# SPI_FRAM_Rev_C.net
KiCad netlist of a schematic drawn in EAGLE
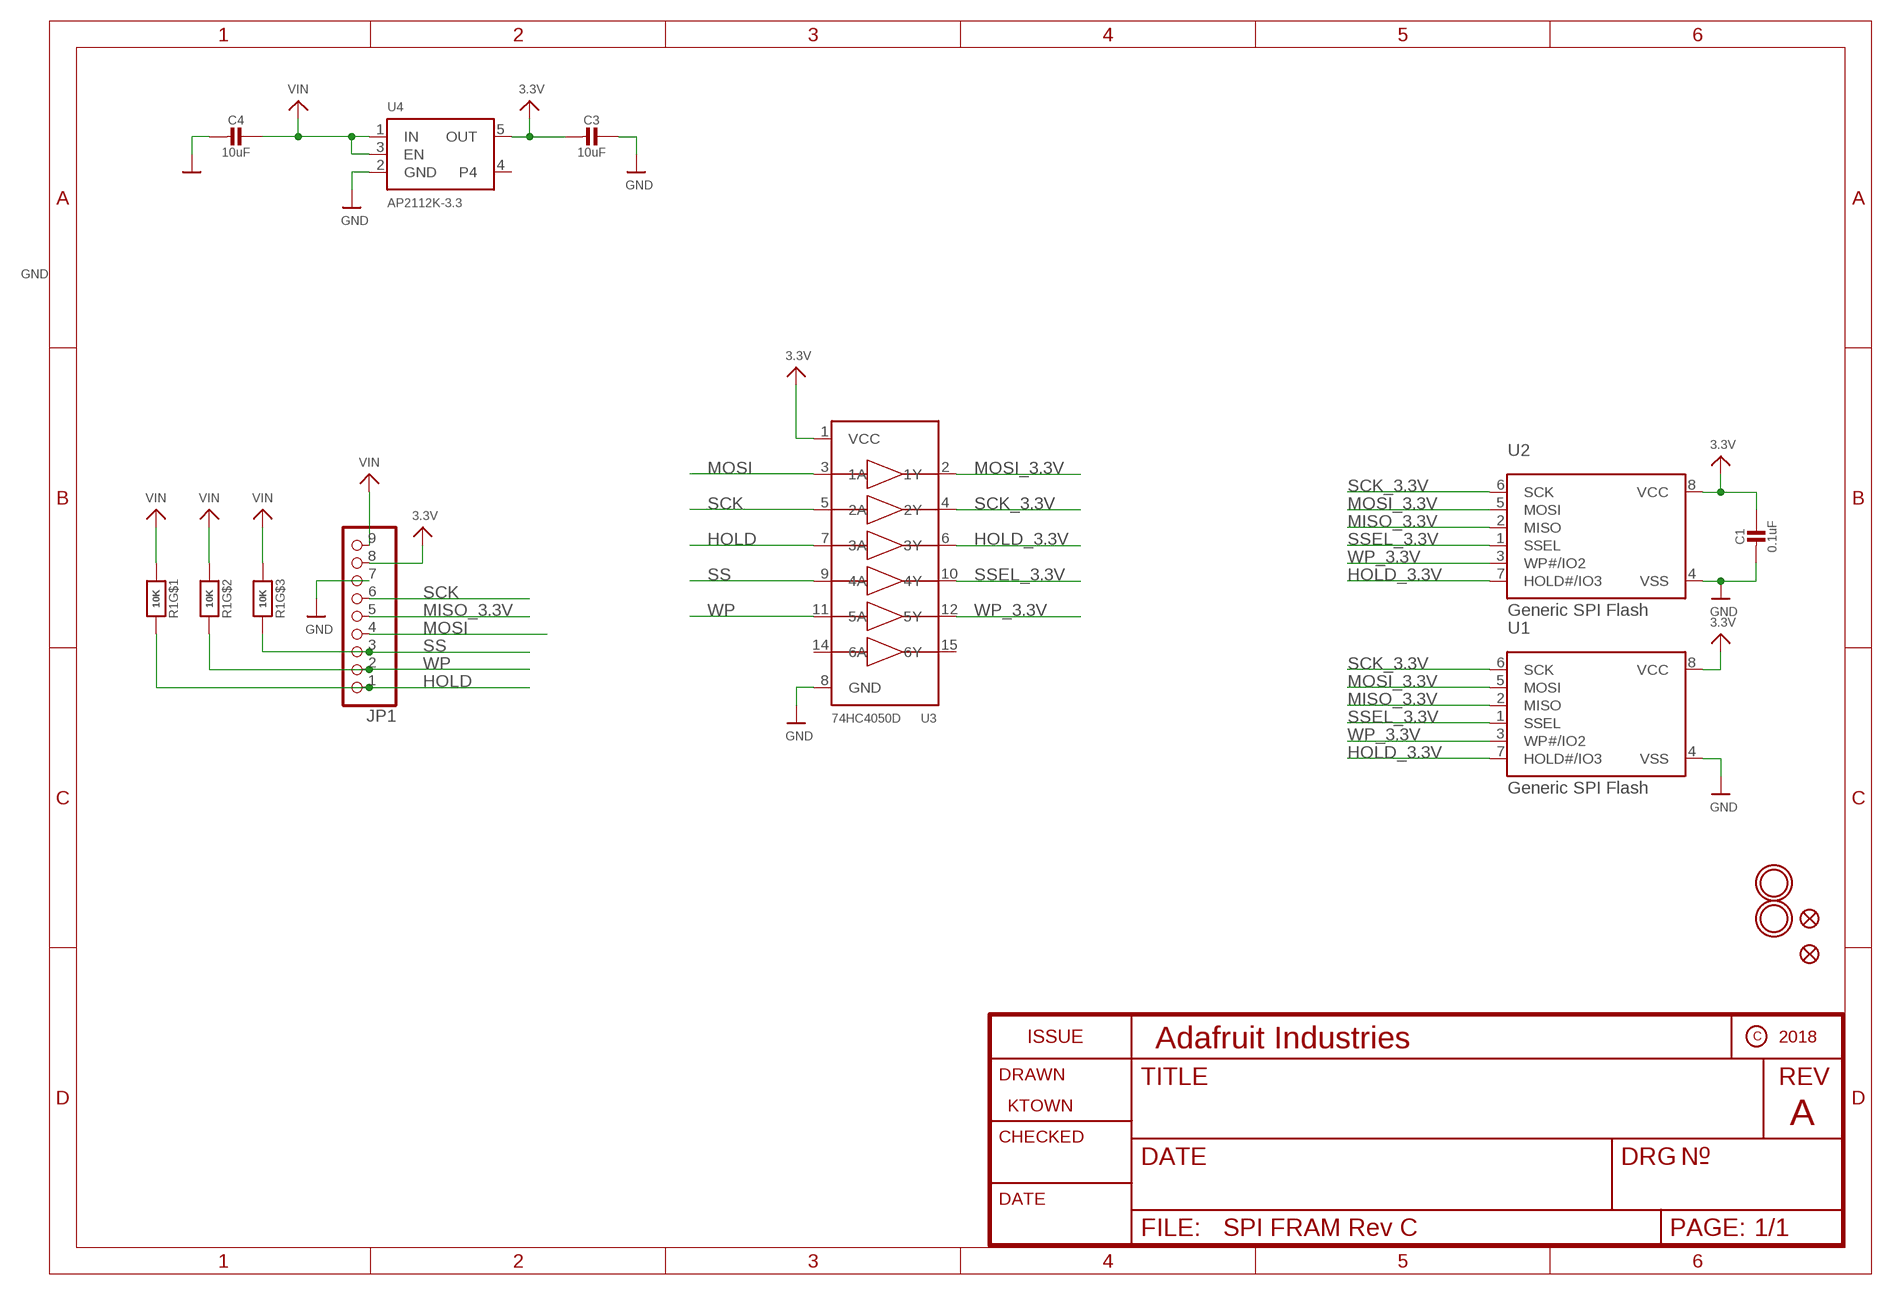
[diagram p0: schematic, sheet 1]

(export (version "E")
  (design (tool "Eeschema 10.0.6"))
  (components
    (comp (ref "C1")
      (value "0.1uF")
      (footprint "eagle-import:0603-NO")
      (libsource (lib "eagle-import") (part "CAP_CERAMIC0603_NO"))
    )
    (comp (ref "C3")
      (value "10uF")
      (footprint "eagle-import:0805-NO")
      (libsource (lib "eagle-import") (part "CAP_CERAMIC0805-NOOUTLINE"))
    )
    (comp (ref "C4")
      (value "10uF")
      (footprint "eagle-import:0805-NO")
      (libsource (lib "eagle-import") (part "CAP_CERAMIC0805-NOOUTLINE"))
    )
    (comp (ref "FID2")
      (value "FIDUCIAL_1MM")
      (footprint "eagle-import:FIDUCIAL_1MM")
      (libsource (lib "eagle-import") (part "FIDUCIAL_1MM"))
    )
    (comp (ref "FID3")
      (value "FIDUCIAL_1MM")
      (footprint "eagle-import:FIDUCIAL_1MM")
      (libsource (lib "eagle-import") (part "FIDUCIAL_1MM"))
    )
    (comp (ref "JP1")
      (value "HEADER-1X970MIL")
      (footprint "eagle-import:1X09_ROUND_70")
      (libsource (lib "eagle-import") (part "HEADER-1X970MIL"))
    )
    (comp (ref "R1")
      (value "10K")
      (footprint "eagle-import:RESPACK_4X0603")
      (libsource (lib "eagle-import") (part "RESISTOR_4PACK"))
    )
    (comp (ref "U$16")
      (value "MOUNTINGHOLE2.5")
      (footprint "eagle-import:MOUNTINGHOLE_2.5_PLATED")
      (libsource (lib "eagle-import") (part "MOUNTINGHOLE2.5"))
    )
    (comp (ref "U$17")
      (value "MOUNTINGHOLE2.5")
      (footprint "eagle-import:MOUNTINGHOLE_2.5_PLATED")
      (libsource (lib "eagle-import") (part "MOUNTINGHOLE2.5"))
    )
    (comp (ref "U1")
      (value "Generic SPI Flash")
      (footprint "eagle-import:SOIC8_208MIL")
      (libsource (lib "eagle-import") (part "SPIFLASH_8PIN208MIL"))
    )
    (comp (ref "U2")
      (value "Generic SPI Flash")
      (footprint "eagle-import:USON8")
      (libsource (lib "eagle-import") (part "SPIFLASH_8PINUX"))
    )
    (comp (ref "U3")
      (value "74HC4050D")
      (footprint "eagle-import:TSSOP16")
      (libsource (lib "eagle-import") (part "74HC4050DTSSOP"))
    )
    (comp (ref "U4")
      (value "AP2112K-3.3")
      (footprint "eagle-import:SOT23-5")
      (libsource (lib "eagle-import") (part "VREG_SOT23-5"))
    )
  )
  (nets
    (net (code "1") (name "/HOLD") (class "Default")
      (node (ref "JP1") (pin "1") (pinfunction "1_1") (pintype "passive"))
      (node (ref "R1") (pin "8") (pinfunction "2_8") (pintype "passive"))
      (node (ref "U3") (pin "7") (pinfunction "3A_7") (pintype "bidirectional"))
    )
    (net (code "2") (name "/HOLD_3.3V") (class "Default")
      (node (ref "U1") (pin "7") (pinfunction "HOLD#/IO3_7") (pintype "bidirectional"))
      (node (ref "U2") (pin "7") (pinfunction "HOLD#/IO3_7") (pintype "bidirectional"))
      (node (ref "U3") (pin "6") (pinfunction "3Y_6") (pintype "bidirectional"))
    )
    (net (code "3") (name "/MISO_3.3V") (class "Default")
      (node (ref "JP1") (pin "5") (pinfunction "5_5") (pintype "passive"))
      (node (ref "U1") (pin "2") (pinfunction "MISO_2") (pintype "bidirectional"))
      (node (ref "U2") (pin "2") (pinfunction "MISO_2") (pintype "bidirectional"))
    )
    (net (code "4") (name "/MOSI") (class "Default")
      (node (ref "JP1") (pin "4") (pinfunction "4_4") (pintype "passive"))
      (node (ref "U3") (pin "3") (pinfunction "1A_3") (pintype "bidirectional"))
    )
    (net (code "5") (name "/MOSI_3.3V") (class "Default")
      (node (ref "U1") (pin "5") (pinfunction "MOSI_5") (pintype "bidirectional"))
      (node (ref "U2") (pin "5") (pinfunction "MOSI_5") (pintype "bidirectional"))
      (node (ref "U3") (pin "2") (pinfunction "1Y_2") (pintype "bidirectional"))
    )
    (net (code "6") (name "/SCK") (class "Default")
      (node (ref "JP1") (pin "6") (pinfunction "6_6") (pintype "passive"))
      (node (ref "U3") (pin "5") (pinfunction "2A_5") (pintype "bidirectional"))
    )
    (net (code "7") (name "/SCK_3.3V") (class "Default")
      (node (ref "U1") (pin "6") (pinfunction "SCK_6") (pintype "bidirectional"))
      (node (ref "U2") (pin "6") (pinfunction "SCK_6") (pintype "bidirectional"))
      (node (ref "U3") (pin "4") (pinfunction "2Y_4") (pintype "bidirectional"))
    )
    (net (code "8") (name "/SS") (class "Default")
      (node (ref "JP1") (pin "3") (pinfunction "3_3") (pintype "passive"))
      (node (ref "R1") (pin "6") (pinfunction "2_6") (pintype "passive"))
      (node (ref "U3") (pin "9") (pinfunction "4A_9") (pintype "bidirectional"))
    )
    (net (code "9") (name "/SSEL_3.3V") (class "Default")
      (node (ref "U1") (pin "1") (pinfunction "SSEL_1") (pintype "bidirectional"))
      (node (ref "U2") (pin "1") (pinfunction "SSEL_1") (pintype "bidirectional"))
      (node (ref "U3") (pin "10") (pinfunction "4Y_10") (pintype "bidirectional"))
    )
    (net (code "10") (name "/WP") (class "Default")
      (node (ref "JP1") (pin "2") (pinfunction "2_2") (pintype "passive"))
      (node (ref "R1") (pin "7") (pinfunction "2_7") (pintype "passive"))
      (node (ref "U3") (pin "11") (pinfunction "5A_11") (pintype "bidirectional"))
    )
    (net (code "11") (name "/WP_3.3V") (class "Default")
      (node (ref "U1") (pin "3") (pinfunction "WP#/IO2_3") (pintype "bidirectional"))
      (node (ref "U2") (pin "3") (pinfunction "WP#/IO2_3") (pintype "bidirectional"))
      (node (ref "U3") (pin "12") (pinfunction "5Y_12") (pintype "bidirectional"))
    )
    (net (code "12") (name "3.3V") (class "Default")
      (node (ref "C1") (pin "1") (pinfunction "1_1") (pintype "passive"))
      (node (ref "C3") (pin "2") (pinfunction "2_2") (pintype "passive"))
      (node (ref "JP1") (pin "8") (pinfunction "8_8") (pintype "passive"))
      (node (ref "U1") (pin "8") (pinfunction "VCC_8") (pintype "bidirectional"))
      (node (ref "U2") (pin "8") (pinfunction "VCC_8") (pintype "bidirectional"))
      (node (ref "U3") (pin "1") (pinfunction "VCC_1") (pintype "bidirectional"))
      (node (ref "U4") (pin "5") (pinfunction "OUT_5") (pintype "power_in"))
    )
    (net (code "13") (name "GND") (class "Default")
      (node (ref "C1") (pin "2") (pinfunction "2_2") (pintype "passive"))
      (node (ref "C3") (pin "1") (pinfunction "1_1") (pintype "passive"))
      (node (ref "C4") (pin "2") (pinfunction "2_2") (pintype "passive"))
      (node (ref "JP1") (pin "7") (pinfunction "7_7") (pintype "passive"))
      (node (ref "U1") (pin "4") (pinfunction "VSS_4") (pintype "bidirectional"))
      (node (ref "U2") (pin "4") (pinfunction "VSS_4") (pintype "bidirectional"))
      (node (ref "U3") (pin "8") (pinfunction "GND_8") (pintype "bidirectional"))
      (node (ref "U4") (pin "2") (pinfunction "GND_2") (pintype "power_in"))
    )
    (net (code "14") (name "VIN") (class "Default")
      (node (ref "C4") (pin "1") (pinfunction "1_1") (pintype "passive"))
      (node (ref "JP1") (pin "9") (pinfunction "9_9") (pintype "passive"))
      (node (ref "R1") (pin "1") (pinfunction "1_1") (pintype "passive"))
      (node (ref "R1") (pin "2") (pinfunction "1_2") (pintype "passive"))
      (node (ref "R1") (pin "3") (pinfunction "1_3") (pintype "passive"))
      (node (ref "U4") (pin "1") (pinfunction "IN_1") (pintype "power_in"))
      (node (ref "U4") (pin "3") (pinfunction "EN_3") (pintype "input"))
    )
    (net (code "15") (name "unconnected-(U3-6A-Pad14)") (class "Default")
      (node (ref "U3") (pin "14") (pinfunction "6A_14") (pintype "bidirectional"))
    )
    (net (code "16") (name "unconnected-(U3-6Y-Pad15)") (class "Default")
      (node (ref "U3") (pin "15") (pinfunction "6Y_15") (pintype "bidirectional"))
    )
    (net (code "17") (name "unconnected-(U4-P4-Pad4)") (class "Default")
      (node (ref "U4") (pin "4") (pinfunction "P4_4") (pintype "bidirectional"))
    )
  )
)
